# FMCio_rowsCDGH.net
KiCad netlist of a schematic drawn in Altium Designer
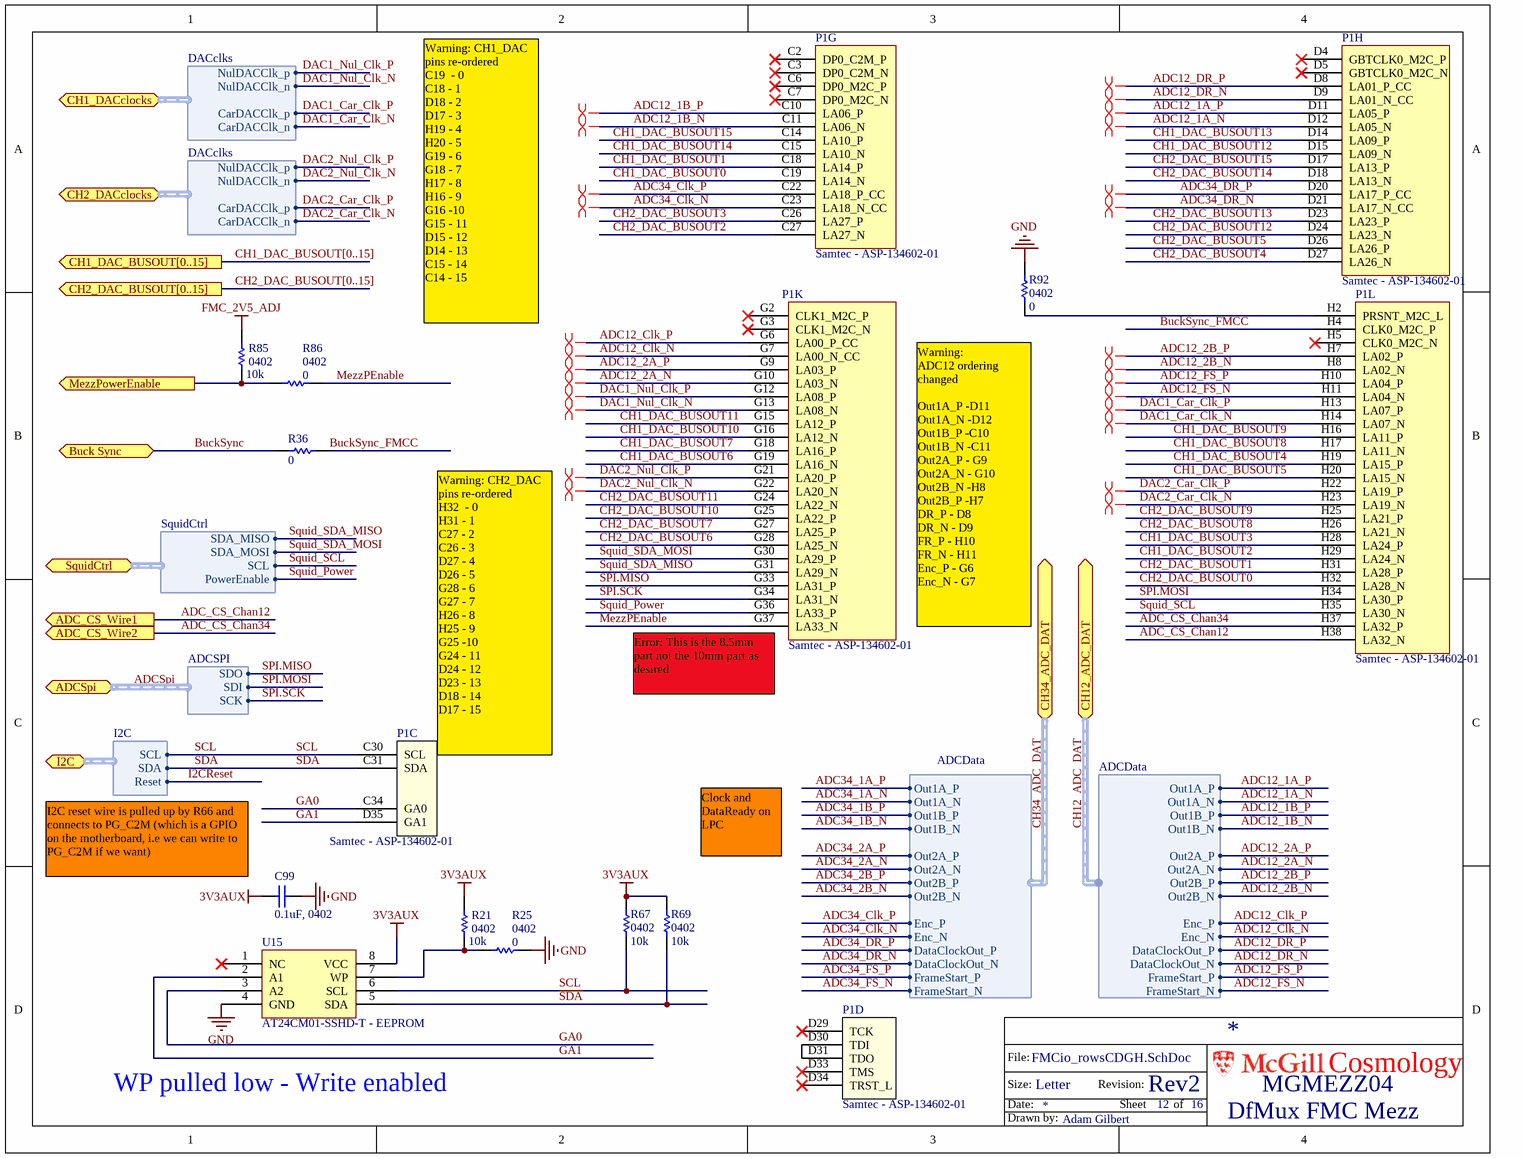
[diagram p0: FMCio_rowsCDGH.SchDoc]

(export (version "E")
  (design (tool "Eeschema 10.0.6"))
  (components
    (comp (ref "C99")
      (value "0.1uF, 0402")
      (footprint "0402")
      (description "Capacitor, Ceramic, 0402")
      (fields (field (name "MANUFACTURER") "TDK Corporation"))
      (libsource (lib "MGMEZZ04") (part "CAP 0603"))
    )
    (comp (ref "P1")
      (value "Samtec - ASP-134602-01")
      (footprint "BTB-SM1-27-2V400M")
      (description "Samtec ASP-134602-01")
      (fields (field (name "MANUFACTURER") "Samtec"))
      (libsource (lib "MGMEZZ04") (part "Samtec - ASP-134602-01"))
    )
    (comp (ref "R21")
      (value "10k")
      (footprint "0402")
      (description "Resistor")
      (fields (field (name "MANUFACTURER") "Generic"))
      (libsource (lib "MGMEZZ04") (part "RES 0402"))
    )
    (comp (ref "R25")
      (value "0")
      (footprint "0402")
      (description "Resistor")
      (fields (field (name "MANUFACTURER") "Generic"))
      (libsource (lib "MGMEZZ04") (part "RES 0402"))
    )
    (comp (ref "R36")
      (value "0")
      (footprint "0805")
      (description "RES 0.0 OHM 1/8W 0805 SMD")
      (fields (field (name "MANUFACTURER") "e.g Vishay/Dale"))
      (libsource (lib "AdamsParts") (part "Res1812"))
    )
    (comp (ref "R67")
      (value "10k")
      (footprint "0402")
      (description "Resistor")
      (fields (field (name "MANUFACTURER") "Generic"))
      (libsource (lib "MGMEZZ04") (part "RES 0402"))
    )
    (comp (ref "R69")
      (value "10k")
      (footprint "0402")
      (description "Resistor")
      (fields (field (name "MANUFACTURER") "Generic"))
      (libsource (lib "MGMEZZ04") (part "RES 0402"))
    )
    (comp (ref "R85")
      (value "10k")
      (footprint "0402")
      (description "Resistor")
      (fields (field (name "MANUFACTURER") "Generic"))
      (libsource (lib "MGMEZZ04") (part "RES 0402"))
    )
    (comp (ref "R86")
      (value "0")
      (footprint "0402")
      (description "Resistor")
      (fields (field (name "MANUFACTURER") "Generic"))
      (libsource (lib "MGMEZZ04") (part "RES 0402"))
    )
    (comp (ref "R92")
      (value "0")
      (footprint "0402")
      (description "Resistor")
      (fields (field (name "MANUFACTURER") "Generic"))
      (libsource (lib "MGMEZZ04") (part "RES 0402"))
    )
    (comp (ref "U15")
      (value "AT24CM01-SSHD-T - EEPROM")
      (footprint "SO8/L200")
      (description "IC EEPROM 1MBIT 1MHZ 8SOIC")
      (fields (field (name "MANUFACTURER") "Atmel"))
      (libsource (lib "AdamsParts") (part "AT24C1024B"))
    )
  )
  (nets
    (net (code "7") (name "/ADC12_1A_N") (class "Default")
      (node (ref "P1") (pin "D12") (pinfunction "LA05_N_D12") (pintype "passive"))
    )
    (net (code "8") (name "/ADC12_1A_P") (class "Default")
      (node (ref "P1") (pin "D11") (pinfunction "LA05_P_D11") (pintype "passive"))
    )
    (net (code "9") (name "/ADC12_1B_N") (class "Default")
      (node (ref "P1") (pin "C11") (pinfunction "LA06_N_C11") (pintype "passive"))
    )
    (net (code "10") (name "/ADC12_1B_P") (class "Default")
      (node (ref "P1") (pin "C10") (pinfunction "LA06_P_C10") (pintype "passive"))
    )
    (net (code "11") (name "/ADC12_2A_N") (class "Default")
      (node (ref "P1") (pin "G10") (pinfunction "LA03_N_G10") (pintype "passive"))
    )
    (net (code "12") (name "/ADC12_2A_P") (class "Default")
      (node (ref "P1") (pin "G9") (pinfunction "LA03_P_G9") (pintype "passive"))
    )
    (net (code "13") (name "/ADC12_2B_N") (class "Default")
      (node (ref "P1") (pin "H8") (pinfunction "LA02_N_H8") (pintype "passive"))
    )
    (net (code "14") (name "/ADC12_2B_P") (class "Default")
      (node (ref "P1") (pin "H7") (pinfunction "LA02_P_H7") (pintype "passive"))
    )
    (net (code "15") (name "/ADC12_Clk_N") (class "Default")
      (node (ref "P1") (pin "G7") (pinfunction "LA00_N_CC_G7") (pintype "passive"))
    )
    (net (code "16") (name "/ADC12_Clk_P") (class "Default")
      (node (ref "P1") (pin "G6") (pinfunction "LA00_P_CC_G6") (pintype "passive"))
    )
    (net (code "17") (name "/ADC12_DR_N") (class "Default")
      (node (ref "P1") (pin "D9") (pinfunction "LA01_N_CC_D9") (pintype "passive"))
    )
    (net (code "18") (name "/ADC12_DR_P") (class "Default")
      (node (ref "P1") (pin "D8") (pinfunction "LA01_P_CC_D8") (pintype "passive"))
    )
    (net (code "19") (name "/ADC12_FS_N") (class "Default")
      (node (ref "P1") (pin "H11") (pinfunction "LA04_N_H11") (pintype "passive"))
    )
    (net (code "20") (name "/ADC12_FS_P") (class "Default")
      (node (ref "P1") (pin "H10") (pinfunction "LA04_P_H10") (pintype "passive"))
    )
    (net (code "29") (name "/ADC34_Clk_N") (class "Default")
      (node (ref "P1") (pin "C23") (pinfunction "LA18_N_CC_C23") (pintype "passive"))
    )
    (net (code "30") (name "/ADC34_Clk_P") (class "Default")
      (node (ref "P1") (pin "C22") (pinfunction "LA18_P_CC_C22") (pintype "passive"))
    )
    (net (code "31") (name "/ADC34_DR_N") (class "Default")
      (node (ref "P1") (pin "D21") (pinfunction "LA17_N_CC_D21") (pintype "passive"))
    )
    (net (code "32") (name "/ADC34_DR_P") (class "Default")
      (node (ref "P1") (pin "D20") (pinfunction "LA17_P_CC_D20") (pintype "passive"))
    )
    (net (code "36") (name "/ADC_CS_Chan12") (class "Default")
      (node (ref "P1") (pin "H38") (pinfunction "LA32_N_H38") (pintype "passive"))
    )
    (net (code "37") (name "/ADC_CS_Chan34") (class "Default")
      (node (ref "P1") (pin "H37") (pinfunction "LA32_P_H37") (pintype "passive"))
    )
    (net (code "38") (name "/BuckSync") (class "Default")
      (node (ref "R36") (pin "2") (pinfunction "2_2") (pintype "passive"))
    )
    (net (code "39") (name "/BuckSync_FMCC") (class "Default")
      (node (ref "P1") (pin "H4") (pinfunction "CLK0_M2C_P_H4") (pintype "passive"))
      (node (ref "R36") (pin "1") (pinfunction "1_1") (pintype "passive"))
    )
    (net (code "40") (name "/CH1_DAC_BUSOUT0") (class "Default")
      (node (ref "P1") (pin "C19") (pinfunction "LA14_N_C19") (pintype "passive"))
    )
    (net (code "41") (name "/CH1_DAC_BUSOUT1") (class "Default")
      (node (ref "P1") (pin "C18") (pinfunction "LA14_P_C18") (pintype "passive"))
    )
    (net (code "42") (name "/CH1_DAC_BUSOUT2") (class "Default")
      (node (ref "P1") (pin "H29") (pinfunction "LA24_N_H29") (pintype "passive"))
    )
    (net (code "43") (name "/CH1_DAC_BUSOUT3") (class "Default")
      (node (ref "P1") (pin "H28") (pinfunction "LA24_P_H28") (pintype "passive"))
    )
    (net (code "44") (name "/CH1_DAC_BUSOUT4") (class "Default")
      (node (ref "P1") (pin "H19") (pinfunction "LA15_P_H19") (pintype "passive"))
    )
    (net (code "45") (name "/CH1_DAC_BUSOUT5") (class "Default")
      (node (ref "P1") (pin "H20") (pinfunction "LA15_N_H20") (pintype "passive"))
    )
    (net (code "46") (name "/CH1_DAC_BUSOUT6") (class "Default")
      (node (ref "P1") (pin "G19") (pinfunction "LA16_N_G19") (pintype "passive"))
    )
    (net (code "47") (name "/CH1_DAC_BUSOUT7") (class "Default")
      (node (ref "P1") (pin "G18") (pinfunction "LA16_P_G18") (pintype "passive"))
    )
    (net (code "48") (name "/CH1_DAC_BUSOUT8") (class "Default")
      (node (ref "P1") (pin "H17") (pinfunction "LA11_N_H17") (pintype "passive"))
    )
    (net (code "49") (name "/CH1_DAC_BUSOUT9") (class "Default")
      (node (ref "P1") (pin "H16") (pinfunction "LA11_P_H16") (pintype "passive"))
    )
    (net (code "50") (name "/CH1_DAC_BUSOUT10") (class "Default")
      (node (ref "P1") (pin "G16") (pinfunction "LA12_N_G16") (pintype "passive"))
    )
    (net (code "51") (name "/CH1_DAC_BUSOUT11") (class "Default")
      (node (ref "P1") (pin "G15") (pinfunction "LA12_P_G15") (pintype "passive"))
    )
    (net (code "52") (name "/CH1_DAC_BUSOUT12") (class "Default")
      (node (ref "P1") (pin "D15") (pinfunction "LA09_N_D15") (pintype "passive"))
    )
    (net (code "53") (name "/CH1_DAC_BUSOUT13") (class "Default")
      (node (ref "P1") (pin "D14") (pinfunction "LA09_P_D14") (pintype "passive"))
    )
    (net (code "54") (name "/CH1_DAC_BUSOUT14") (class "Default")
      (node (ref "P1") (pin "C15") (pinfunction "LA10_N_C15") (pintype "passive"))
    )
    (net (code "55") (name "/CH1_DAC_BUSOUT15") (class "Default")
      (node (ref "P1") (pin "C14") (pinfunction "LA10_P_C14") (pintype "passive"))
    )
    (net (code "57") (name "/CH2_DAC_BUSOUT0") (class "Default")
      (node (ref "P1") (pin "H32") (pinfunction "LA28_N_H32") (pintype "passive"))
    )
    (net (code "58") (name "/CH2_DAC_BUSOUT1") (class "Default")
      (node (ref "P1") (pin "H31") (pinfunction "LA28_P_H31") (pintype "passive"))
    )
    (net (code "59") (name "/CH2_DAC_BUSOUT2") (class "Default")
      (node (ref "P1") (pin "C27") (pinfunction "LA27_N_C27") (pintype "passive"))
    )
    (net (code "60") (name "/CH2_DAC_BUSOUT3") (class "Default")
      (node (ref "P1") (pin "C26") (pinfunction "LA27_P_C26") (pintype "passive"))
    )
    (net (code "61") (name "/CH2_DAC_BUSOUT4") (class "Default")
      (node (ref "P1") (pin "D27") (pinfunction "LA26_N_D27") (pintype "passive"))
    )
    (net (code "62") (name "/CH2_DAC_BUSOUT5") (class "Default")
      (node (ref "P1") (pin "D26") (pinfunction "LA26_P_D26") (pintype "passive"))
    )
    (net (code "63") (name "/CH2_DAC_BUSOUT6") (class "Default")
      (node (ref "P1") (pin "G28") (pinfunction "LA25_N_G28") (pintype "passive"))
    )
    (net (code "64") (name "/CH2_DAC_BUSOUT7") (class "Default")
      (node (ref "P1") (pin "G27") (pinfunction "LA25_P_G27") (pintype "passive"))
    )
    (net (code "65") (name "/CH2_DAC_BUSOUT8") (class "Default")
      (node (ref "P1") (pin "H26") (pinfunction "LA21_N_H26") (pintype "passive"))
    )
    (net (code "66") (name "/CH2_DAC_BUSOUT9") (class "Default")
      (node (ref "P1") (pin "H25") (pinfunction "LA21_P_H25") (pintype "passive"))
    )
    (net (code "67") (name "/CH2_DAC_BUSOUT10") (class "Default")
      (node (ref "P1") (pin "G25") (pinfunction "LA22_P_G25") (pintype "passive"))
    )
    (net (code "68") (name "/CH2_DAC_BUSOUT11") (class "Default")
      (node (ref "P1") (pin "G24") (pinfunction "LA22_N_G24") (pintype "passive"))
    )
    (net (code "69") (name "/CH2_DAC_BUSOUT12") (class "Default")
      (node (ref "P1") (pin "D24") (pinfunction "LA23_N_D24") (pintype "passive"))
    )
    (net (code "70") (name "/CH2_DAC_BUSOUT13") (class "Default")
      (node (ref "P1") (pin "D23") (pinfunction "LA23_P_D23") (pintype "passive"))
    )
    (net (code "71") (name "/CH2_DAC_BUSOUT14") (class "Default")
      (node (ref "P1") (pin "D18") (pinfunction "LA13_N_D18") (pintype "passive"))
    )
    (net (code "72") (name "/CH2_DAC_BUSOUT15") (class "Default")
      (node (ref "P1") (pin "D17") (pinfunction "LA13_P_D17") (pintype "passive"))
    )
    (net (code "76") (name "/DAC1_Car_Clk_N") (class "Default")
      (node (ref "P1") (pin "H14") (pinfunction "LA07_N_H14") (pintype "passive"))
    )
    (net (code "77") (name "/DAC1_Car_Clk_P") (class "Default")
      (node (ref "P1") (pin "H13") (pinfunction "LA07_P_H13") (pintype "passive"))
    )
    (net (code "78") (name "/DAC1_Nul_Clk_N") (class "Default")
      (node (ref "P1") (pin "G13") (pinfunction "LA08_N_G13") (pintype "passive"))
    )
    (net (code "79") (name "/DAC1_Nul_Clk_P") (class "Default")
      (node (ref "P1") (pin "G12") (pinfunction "LA08_P_G12") (pintype "passive"))
    )
    (net (code "80") (name "/DAC2_Car_Clk_N") (class "Default")
      (node (ref "P1") (pin "H23") (pinfunction "LA19_N_H23") (pintype "passive"))
    )
    (net (code "81") (name "/DAC2_Car_Clk_P") (class "Default")
      (node (ref "P1") (pin "H22") (pinfunction "LA19_P_H22") (pintype "passive"))
    )
    (net (code "82") (name "/DAC2_Nul_Clk_N") (class "Default")
      (node (ref "P1") (pin "G22") (pinfunction "LA20_N_G22") (pintype "passive"))
    )
    (net (code "83") (name "/DAC2_Nul_Clk_P") (class "Default")
      (node (ref "P1") (pin "G21") (pinfunction "LA20_P_G21") (pintype "passive"))
    )
    (net (code "84") (name "/GA0") (class "Default")
      (node (ref "P1") (pin "C34") (pinfunction "GA0_C34") (pintype "passive"))
      (node (ref "U15") (pin "3") (pinfunction "A2_3") (pintype "passive"))
    )
    (net (code "85") (name "/GA1") (class "Default")
      (node (ref "P1") (pin "D35") (pinfunction "GA1_D35") (pintype "passive"))
      (node (ref "U15") (pin "2") (pinfunction "A1_2") (pintype "passive"))
    )
    (net (code "87") (name "/MezzPEnable") (class "Default")
      (node (ref "P1") (pin "G37") (pinfunction "LA33_N_G37") (pintype "passive"))
      (node (ref "R86") (pin "2") (pinfunction "2_2") (pintype "passive"))
    )
    (net (code "88") (name "/MezzPowerEnable") (class "Default")
      (node (ref "R85") (pin "2") (pinfunction "2_2") (pintype "passive"))
      (node (ref "R86") (pin "1") (pinfunction "1_1") (pintype "passive"))
    )
    (net (code "89") (name "/SCL") (class "Default")
      (node (ref "P1") (pin "C30") (pinfunction "SCL_C30") (pintype "passive"))
      (node (ref "R67") (pin "2") (pinfunction "2_2") (pintype "passive"))
      (node (ref "U15") (pin "6") (pinfunction "SCL_6") (pintype "passive"))
    )
    (net (code "90") (name "/SDA") (class "Default")
      (node (ref "P1") (pin "C31") (pinfunction "SDA_C31") (pintype "passive"))
      (node (ref "R69") (pin "2") (pinfunction "2_2") (pintype "passive"))
      (node (ref "U15") (pin "5") (pinfunction "SDA_5") (pintype "passive"))
    )
    (net (code "91") (name "/SPI.MISO") (class "Default")
      (node (ref "P1") (pin "G33") (pinfunction "LA31_P_G33") (pintype "passive"))
    )
    (net (code "92") (name "/SPI.MOSI") (class "Default")
      (node (ref "P1") (pin "H34") (pinfunction "LA30_P_H34") (pintype "passive"))
    )
    (net (code "93") (name "/SPI.SCK") (class "Default")
      (node (ref "P1") (pin "G34") (pinfunction "LA31_N_G34") (pintype "passive"))
    )
    (net (code "94") (name "/Squid_Power") (class "Default")
      (node (ref "P1") (pin "G36") (pinfunction "LA33_P_G36") (pintype "passive"))
    )
    (net (code "95") (name "/Squid_SCL") (class "Default")
      (node (ref "P1") (pin "H35") (pinfunction "LA30_N_H35") (pintype "passive"))
    )
    (net (code "96") (name "/Squid_SDA_MISO") (class "Default")
      (node (ref "P1") (pin "G31") (pinfunction "LA29_N_G31") (pintype "passive"))
    )
    (net (code "97") (name "/Squid_SDA_MOSI") (class "Default")
      (node (ref "P1") (pin "G30") (pinfunction "LA29_P_G30") (pintype "passive"))
    )
    (net (code "101") (name "3V3AUX") (class "Default")
      (node (ref "C99") (pin "1") (pinfunction "1_1") (pintype "passive"))
      (node (ref "R21") (pin "1") (pinfunction "1_1") (pintype "passive"))
      (node (ref "R67") (pin "1") (pinfunction "1_1") (pintype "passive"))
      (node (ref "R69") (pin "1") (pinfunction "1_1") (pintype "passive"))
      (node (ref "U15") (pin "8") (pinfunction "VCC_8") (pintype "passive"))
    )
    (net (code "102") (name "FMC_2V5_ADJ") (class "Default")
      (node (ref "R85") (pin "1") (pinfunction "1_1") (pintype "passive"))
    )
    (net (code "103") (name "GND") (class "Default")
      (node (ref "C99") (pin "2") (pinfunction "2_2") (pintype "passive"))
      (node (ref "R25") (pin "2") (pinfunction "2_2") (pintype "passive"))
      (node (ref "R92") (pin "2") (pinfunction "2_2") (pintype "passive"))
      (node (ref "U15") (pin "4") (pinfunction "GND_4") (pintype "passive"))
    )
    (net (code "104") (name "Net-(P1D-TDI)") (class "Default")
      (node (ref "P1") (pin "D30") (pinfunction "TDI_D30") (pintype "passive"))
      (node (ref "P1") (pin "D31") (pinfunction "TDO_D31") (pintype "passive"))
    )
    (net (code "105") (name "Net-(P1L-PRSNT_M2C_L)") (class "Default")
      (node (ref "P1") (pin "H2") (pinfunction "PRSNT_M2C_L_H2") (pintype "passive"))
      (node (ref "R92") (pin "1") (pinfunction "1_1") (pintype "passive"))
    )
    (net (code "106") (name "Net-(U15-WP)") (class "Default")
      (node (ref "R21") (pin "2") (pinfunction "2_2") (pintype "passive"))
      (node (ref "R25") (pin "1") (pinfunction "1_1") (pintype "passive"))
      (node (ref "U15") (pin "7") (pinfunction "WP_7") (pintype "passive"))
    )
    (net (code "107") (name "unconnected-(P1D-TCK-PadD29)") (class "Default")
      (node (ref "P1") (pin "D29") (pinfunction "TCK_D29") (pintype "passive+no_connect"))
    )
    (net (code "108") (name "unconnected-(P1D-TMS-PadD33)") (class "Default")
      (node (ref "P1") (pin "D33") (pinfunction "TMS_D33") (pintype "passive+no_connect"))
    )
    (net (code "109") (name "unconnected-(P1D-TRST_L-PadD34)") (class "Default")
      (node (ref "P1") (pin "D34") (pinfunction "TRST_L_D34") (pintype "passive+no_connect"))
    )
    (net (code "110") (name "unconnected-(P1G-DP0_C2M_N-PadC3)") (class "Default")
      (node (ref "P1") (pin "C3") (pinfunction "DP0_C2M_N_C3") (pintype "passive+no_connect"))
    )
    (net (code "111") (name "unconnected-(P1G-DP0_C2M_P-PadC2)") (class "Default")
      (node (ref "P1") (pin "C2") (pinfunction "DP0_C2M_P_C2") (pintype "passive+no_connect"))
    )
    (net (code "112") (name "unconnected-(P1G-DP0_M2C_N-PadC7)") (class "Default")
      (node (ref "P1") (pin "C7") (pinfunction "DP0_M2C_N_C7") (pintype "passive+no_connect"))
    )
    (net (code "113") (name "unconnected-(P1G-DP0_M2C_P-PadC6)") (class "Default")
      (node (ref "P1") (pin "C6") (pinfunction "DP0_M2C_P_C6") (pintype "passive+no_connect"))
    )
    (net (code "114") (name "unconnected-(P1H-GBTCLK0_M2C_N-PadD5)") (class "Default")
      (node (ref "P1") (pin "D5") (pinfunction "GBTCLK0_M2C_N_D5") (pintype "passive+no_connect"))
    )
    (net (code "115") (name "unconnected-(P1H-GBTCLK0_M2C_P-PadD4)") (class "Default")
      (node (ref "P1") (pin "D4") (pinfunction "GBTCLK0_M2C_P_D4") (pintype "passive+no_connect"))
    )
    (net (code "116") (name "unconnected-(P1K-CLK1_M2C_N-PadG3)") (class "Default")
      (node (ref "P1") (pin "G3") (pinfunction "CLK1_M2C_N_G3") (pintype "passive+no_connect"))
    )
    (net (code "117") (name "unconnected-(P1K-CLK1_M2C_P-PadG2)") (class "Default")
      (node (ref "P1") (pin "G2") (pinfunction "CLK1_M2C_P_G2") (pintype "passive+no_connect"))
    )
    (net (code "118") (name "unconnected-(P1L-CLK0_M2C_N-PadH5)") (class "Default")
      (node (ref "P1") (pin "H5") (pinfunction "CLK0_M2C_N_H5") (pintype "passive+no_connect"))
    )
    (net (code "119") (name "unconnected-(U15-NC-Pad1)") (class "Default")
      (node (ref "U15") (pin "1") (pinfunction "NC_1") (pintype "passive+no_connect"))
    )
  )
)
